# 18V_Jetson.net
KiCad netlist of a schematic drawn in Altium Designer
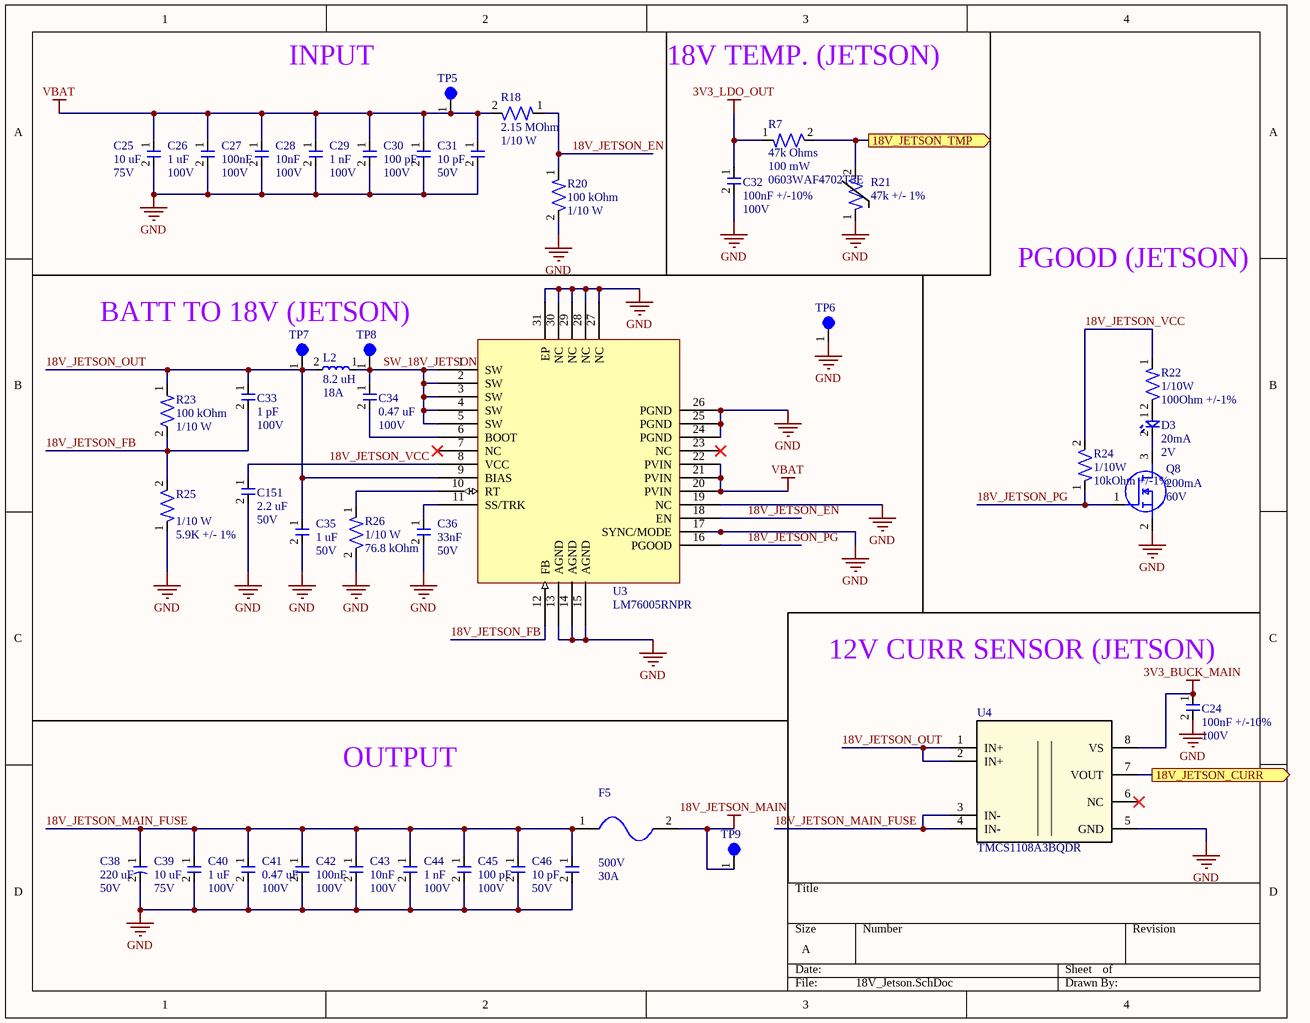
[diagram p0: 18V_Jetson.SchDoc]

(export (version "E")
  (design (tool "Eeschema 10.0.6"))
  (components
    (comp (ref "C24")
      (value "CC0603KRX7R0BB104")
      (footprint "CAP-0603")
      (description "CAP CER 0.1UF 100V X7R 0603")
      (fields
        (field (name "MANUFACTURER") "YAGEO")
        (field (name "CAPACITANCE") "100nF +/-10%")
        (field (name "VOLTAGE RATING") "100V")
      )
      (libsource (lib "MasterLib") (part "CAP-100N-0001"))
    )
    (comp (ref "C25")
      (value "C3225X7R1N106K250AC")
      (footprint "CAP-1210")
      (description "10 µF ±10% 75V Ceramic Capacitor X7R 1210 (3225 Metric)")
      (fields (field (name "CAPACITANCE") "10 uF") (field (name "VOLTAGE RATING") "75V"))
      (libsource (lib "MasterLib") (part "CAP-10U-0004"))
    )
    (comp (ref "C26")
      (value "CL31B105KCHNNNE")
      (footprint "CAP-1206 - duplicate")
      (description "1 µF ±10% 100V Ceramic Capacitor X7R 1206 (3216 Metric)")
      (fields (field (name "CAPACITANCE") "1 uF") (field (name "VOLTAGE") "100V"))
      (libsource (lib "MasterLib") (part "CAP-1U-0001"))
    )
    (comp (ref "C27")
      (value "CC0603KRX7R0BB104")
      (footprint "CAP-0603")
      (description "CAP CER 0.1UF 100V X7R 0603")
      (fields
        (field (name "MANUFACTURER") "YAGEO")
        (field (name "CAPACITANCE") "100nF")
        (field (name "VOLTAGE RATING") "100V")
      )
      (libsource (lib "MasterLib") (part "CAP-100N-0001"))
    )
    (comp (ref "C28")
      (value "C1608C0G2A103J080AC")
      (footprint "CAP-0603")
      (description "CAP CER 10000PF 100V C0G 0603")
      (fields
        (field (name "MANUFACTURER") "TDK Corporation")
        (field (name "CAPACITANCE") "10nF")
        (field (name "VOLTAGE RATING") "100V")
      )
      (libsource (lib "MasterLib") (part "CAP-10N-0002"))
    )
    (comp (ref "C29")
      (value "C0603Y102K1RAC7867")
      (footprint "CAP-0603")
      (description "1000 pF ±10% 100V Ceramic Capacitor X7R 0603 (1608 Metric)")
      (fields (field (name "CAPACITANCE") "1 nF") (field (name "VOLTAGE") "100V"))
      (libsource (lib "MasterLib") (part "CAP-1N-0001"))
    )
    (comp (ref "C30")
      (value "0603N101J101CT")
      (footprint "CAP-0603")
      (description "100 pF ±5% 100V Ceramic Capacitor C0G, NP0 0603 (1608 Metric)")
      (fields
        (field (name "TOLERANCE") "+/-5%")
        (field (name "CAPACITANCE") "100 pF")
        (field (name "VOLTAGE") "100V")
      )
      (libsource (lib "MasterLib") (part "CAP-100P-0002"))
    )
    (comp (ref "C31")
      (value "0603N100J500CT")
      (footprint "CAP-0603")
      (description "10 pF ±5% 50V Ceramic Capacitor C0G, NP0 0603 (1608 Metric)")
      (fields
        (field (name "MANUFACTURER") "Walshin Technology Corporation")
        (field (name "CAPACITANCE") "10 pF")
        (field (name "VOLTAGE RATING") "50V")
      )
      (libsource (lib "MasterLib") (part "CAP-10P-0001"))
    )
    (comp (ref "C32")
      (value "CC0603KRX7R0BB104")
      (footprint "CAP-0603")
      (description "CAP CER 0.1UF 100V X7R 0603")
      (fields
        (field (name "MANUFACTURER") "YAGEO")
        (field (name "CAPACITANCE") "100nF +/-10%")
        (field (name "VOLTAGE RATING") "100V")
      )
      (libsource (lib "MasterLib") (part "CAP-100N-0001"))
    )
    (comp (ref "C33")
      (value "885012006087")
      (footprint "CAP-0603")
      (description "1 pF ±0.25pF 100V Ceramic Capacitor C0G, NP0 0603 (1608 Metric)")
      (fields
        (field (name "TOLERANCE") "+/- 0.25 pF")
        (field (name "CAPACITANCE") "1 pF")
        (field (name "VOLTAGE") "100V")
      )
      (libsource (lib "MasterLib") (part "CAP-1P-0001"))
    )
    (comp (ref "C34")
      (value "KAM21KR72A474KL")
      (footprint "CAP-0805")
      (description "0.47 µF ±10% 100V Ceramic Capacitor X7R 0805 (2012 Metric)")
      (fields
        (field (name "TOLERANCE") "+/- 10%")
        (field (name "CAPACITANCE") "0.47 uF")
        (field (name "VOLTAGE") "100V")
      )
      (libsource (lib "MasterLib") (part "CAP-0.47U-0001"))
    )
    (comp (ref "C35")
      (value "UMK107AB7105KA-T")
      (footprint "CAP-0603")
      (description "1 µF ±10% 50V Ceramic Capacitor X7R 0603 (1608 Metric)")
      (fields (field (name "CAPACITANCE") "1 uF") (field (name "VOLTAGE") "50V"))
      (libsource (lib "MasterLib") (part "CAP-1U-0002"))
    )
    (comp (ref "C36")
      (value "CC0603KRX7R9BB333")
      (footprint "CAP-0603")
      (description "0.033 µF ±10% 50V Ceramic Capacitor X7R 0603 (1608 Metric)")
      (fields
        (field (name "MANUFACTURER") "YAGEO")
        (field (name "CAPACITANCE") "33nF")
        (field (name "VOLTAGE RATING") "50V")
      )
      (libsource (lib "MasterLib") (part "CAP-33N-0001"))
    )
    (comp (ref "C38")
      (value "50TZV220M10X10.5")
      (footprint "ELEC-220U-0003")
      (description "220 µF 50 V Aluminum Electrolytic Capacitors Radial, Can - SMD 2000 Hrs @ 105°C")
      (fields (field (name "CAPACITANCE") "220 uF") (field (name "VOLTAGE RATING") "50V"))
      (libsource (lib "MasterLib") (part "ELEC-220U-0003"))
    )
    (comp (ref "C39")
      (value "C3225X7R1N106K250AC")
      (footprint "CAP-1210")
      (description "10 µF ±10% 75V Ceramic Capacitor X7R 1210 (3225 Metric)")
      (fields (field (name "CAPACITANCE") "10 uF") (field (name "VOLTAGE RATING") "75V"))
      (libsource (lib "MasterLib") (part "CAP-10U-0004"))
    )
    (comp (ref "C40")
      (value "CL31B105KCHNNNE")
      (footprint "CAP-1206 - duplicate")
      (description "1 µF ±10% 100V Ceramic Capacitor X7R 1206 (3216 Metric)")
      (fields (field (name "CAPACITANCE") "1 uF") (field (name "VOLTAGE") "100V"))
      (libsource (lib "MasterLib") (part "CAP-1U-0001"))
    )
    (comp (ref "C41")
      (value "KAM21KR72A474KL")
      (footprint "CAP-0805")
      (description "0.47 µF ±10% 100V Ceramic Capacitor X7R 0805 (2012 Metric)")
      (fields
        (field (name "TOLERANCE") "+/- 10%")
        (field (name "CAPACITANCE") "0.47 uF")
        (field (name "VOLTAGE") "100V")
      )
      (libsource (lib "MasterLib") (part "CAP-0.47U-0001"))
    )
    (comp (ref "C42")
      (value "CC0603KRX7R0BB104")
      (footprint "CAP-0603")
      (description "CAP CER 0.1UF 100V X7R 0603")
      (fields
        (field (name "MANUFACTURER") "YAGEO")
        (field (name "CAPACITANCE") "100nF")
        (field (name "VOLTAGE RATING") "100V")
      )
      (libsource (lib "MasterLib") (part "CAP-100N-0001"))
    )
    (comp (ref "C43")
      (value "C1608C0G2A103J080AC")
      (footprint "CAP-0603")
      (description "CAP CER 10000PF 100V C0G 0603")
      (fields
        (field (name "MANUFACTURER") "TDK Corporation")
        (field (name "CAPACITANCE") "10nF")
        (field (name "VOLTAGE RATING") "100V")
      )
      (libsource (lib "MasterLib") (part "CAP-10N-0002"))
    )
    (comp (ref "C44")
      (value "C0603Y102K1RAC7867")
      (footprint "CAP-0603")
      (description "1000 pF ±10% 100V Ceramic Capacitor X7R 0603 (1608 Metric)")
      (fields (field (name "CAPACITANCE") "1 nF") (field (name "VOLTAGE") "100V"))
      (libsource (lib "MasterLib") (part "CAP-1N-0001"))
    )
    (comp (ref "C45")
      (value "0603N101J101CT")
      (footprint "CAP-0603")
      (description "100 pF ±5% 100V Ceramic Capacitor C0G, NP0 0603 (1608 Metric)")
      (fields
        (field (name "TOLERANCE") "+/-5%")
        (field (name "CAPACITANCE") "100 pF")
        (field (name "VOLTAGE") "100V")
      )
      (libsource (lib "MasterLib") (part "CAP-100P-0002"))
    )
    (comp (ref "C46")
      (value "0603N100J500CT")
      (footprint "CAP-0603")
      (description "10 pF ±5% 50V Ceramic Capacitor C0G, NP0 0603 (1608 Metric)")
      (fields
        (field (name "MANUFACTURER") "Walshin Technology Corporation")
        (field (name "CAPACITANCE") "10 pF")
        (field (name "VOLTAGE RATING") "50V")
      )
      (libsource (lib "MasterLib") (part "CAP-10P-0001"))
    )
    (comp (ref "C151")
      (value "UMK107BBJ225KA-T")
      (footprint "CAP-0603")
      (description "2.2 µF ±10% 50V Ceramic Capacitor X5R 0603 (1608 Metric)")
      (fields (field (name "CAPACITANCE") "2.2 uF") (field (name "OLTAGE") "50V"))
      (libsource (lib "MasterLib") (part "CAP-2.2U-0001"))
    )
    (comp (ref "D3")
      (value "150060AS75000")
      (footprint "LED-0603")
      (description "CAP CER 0.1UF 100V X7R 0603")
      (fields
        (field (name "MANUFACTURER") "Wurth Electronik")
        (field (name "CURRENT RATING") "20mA")
        (field (name "VF") "2V")
      )
      (libsource (lib "MasterLib") (part "LED_Amber_0001"))
    )
    (comp (ref "F5")
      (value "3568")
      (footprint "FUSE-ATM-0001")
      (description "Fuse Holder 30 A 500V 1 Circuit Blade Through Hole")
      (fields (field (name "VOLTAGE RATING") "500V") (field (name "CURRENT") "30A"))
      (libsource (lib "MasterLib") (part "FUSE-ATM-0001"))
    )
    (comp (ref "L2")
      (value "IHLP6767GZER8R2M01")
      (footprint "PWRIND-8.2U-0002")
      (description "8.2 µH Shielded Molded Inductor 18 A 10.66mOhm Max Nonstandard")
      (fields
        (field (name "TOLERANCE") "+/-20%")
        (field (name "INDUCTANCE") "8.2 uH")
        (field (name "DCI") "18A")
      )
      (libsource (lib "MasterLib") (part "PWRIND-8.2U-0002"))
    )
    (comp (ref "Q8")
      (value "T2N7002AK,LM")
      (footprint "NMOS-SOT23-3")
      (description "MOSFET N-CH 60V 200MA SOT23")
      (fields
        (field (name "MANUFACTURER") "Toshiba")
        (field (name "ID-CONTINUOUS") "200mA")
        (field (name "VDS-MAX") "60V")
      )
      (libsource (lib "MasterLib") (part "NMOS-200MA-0001"))
    )
    (comp (ref "R7")
      (value "0603WAF4702T5E")
      (footprint "RES-0603")
      (description "100mW Thick Film Resistors 75V ±100ppm/℃ ±1% 47kΩ 0603 Chip Resistor - Surface Mount ROHS")
      (fields (field (name "POWER") "100mW"))
      (libsource (lib "MasterLib") (part "RES-47k-0001-JLC"))
    )
    (comp (ref "R18")
      (value "RC0603FR-072M15L")
      (footprint "RES-0603")
      (description "2.15 MOhms ±1% 0.1W, 1/10W Chip Resistor 0603 (1608 Metric) Moisture Resistant Thick Film")
      (fields
        (field (name "TOLERANCE") "+/-1%")
        (field (name "RESISTANCE") "2.15 MOhm")
        (field (name "POWER") "1/10 W")
      )
      (libsource (lib "MasterLib") (part "RES-2.15M-0001"))
    )
    (comp (ref "R20")
      (value "RC0603FR-07100KL")
      (footprint "RES-0603")
      (description "100 kOhms ±1% 0.1W, 1/10W Chip Resistor 0603 (1608 Metric) Moisture Resistant Thick Film")
      (fields
        (field (name "TOLERANCE") "+/- 1%")
        (field (name "RESISTANCE") "100 kOhm")
        (field (name "POWER") "1/10 W")
      )
      (libsource (lib "MasterLib") (part "RES-100K-0003"))
    )
    (comp (ref "R21")
      (value "TMP6431DECR")
      (footprint "RES-0402")
      (description "PTC Thermistor 47 kOhms 0402 (1006 Metric)")
      (fields (field (name "MANUFACTURER") "Texas Instruments") (field (name "RESISTANCE") "47k +/- 1%"))
      (libsource (lib "MasterLib") (part "THERM-47K-0001"))
    )
    (comp (ref "R22")
      (value "AC0603FR-10100RL")
      (footprint "RES-0603")
      (description "100 Ohms ±1% 0.1W, 1/10W Chip Resistor 0603 (1608 Metric) Automotive AEC-Q200 Thick Film")
      (fields
        (field (name "MANUFACTURER") "YAGEO")
        (field (name "POWER RATING") "1/10W")
        (field (name "RESISTANCE") "100Ohm +/-1%")
      )
      (libsource (lib "MasterLib") (part "RES-100-0002"))
    )
    (comp (ref "R23")
      (value "RC0603FR-07100KL")
      (footprint "RES-0603")
      (description "100 kOhms ±1% 0.1W, 1/10W Chip Resistor 0603 (1608 Metric) Moisture Resistant Thick Film")
      (fields
        (field (name "TOLERANCE") "+/- 1%")
        (field (name "RESISTANCE") "100 kOhm")
        (field (name "POWER") "1/10 W")
      )
      (libsource (lib "MasterLib") (part "RES-100K-0003"))
    )
    (comp (ref "R24")
      (value "RC0603FR-0710KP")
      (footprint "RES-0603")
      (description "RES SMD 10K OHM 1% 1/10W 0603")
      (fields
        (field (name "MANUFACTURER") "YAGEO")
        (field (name "POWER RATING") "1/10W")
        (field (name "RESISTANCE") "10kOhm +/-1%")
      )
      (libsource (lib "MasterLib") (part "RES-10K-0002"))
    )
    (comp (ref "R25")
      (value "RC0603FR-075K9L")
      (footprint "RES-0603")
      (description "RES 5.9K OHM 1% 1/10W 0603")
      (fields (field (name "POWER") "1/10 W") (field (name "RESISTANCE") "5.9K +/- 1%"))
      (libsource (lib "MasterLib") (part "RES-5.9K-0001"))
    )
    (comp (ref "R26")
      (value "RC0603FR-0776K8L")
      (footprint "RES-0603")
      (description "76.8 kOhms ±1% 0.1W, 1/10W Chip Resistor 0603 (1608 Metric) Moisture Resistant Thick Film")
      (fields
        (field (name "MANUFACTURER") "Yageo")
        (field (name "TOLERANCE") "+/- 1%")
        (field (name "POWER") "1/10 W")
        (field (name "RESISTANCE") "76.8 kOhm")
      )
      (libsource (lib "MasterLib") (part "RES-76.8K-0001"))
    )
    (comp (ref "TP5")
      (value "5003")
      (footprint "TEST-POINT-0001")
      (description "Oranange PC Test Point, Miniature Phoisphor Bronze Silver Plating Through Hole Mounting Type")
      (libsource (lib "MasterLib") (part "TEST-POINT-0001"))
    )
    (comp (ref "TP6")
      (value "5003")
      (footprint "TEST-POINT-0001")
      (description "Oranange PC Test Point, Miniature Phoisphor Bronze Silver Plating Through Hole Mounting Type")
      (libsource (lib "MasterLib") (part "TEST-POINT-0001"))
    )
    (comp (ref "TP7")
      (value "5003")
      (footprint "TEST-POINT-0001")
      (description "Oranange PC Test Point, Miniature Phoisphor Bronze Silver Plating Through Hole Mounting Type")
      (libsource (lib "MasterLib") (part "TEST-POINT-0001"))
    )
    (comp (ref "TP8")
      (value "5003")
      (footprint "TEST-POINT-0001")
      (description "Oranange PC Test Point, Miniature Phoisphor Bronze Silver Plating Through Hole Mounting Type")
      (libsource (lib "MasterLib") (part "TEST-POINT-0001"))
    )
    (comp (ref "TP9")
      (value "5003")
      (footprint "TEST-POINT-0001")
      (description "Oranange PC Test Point, Miniature Phoisphor Bronze Silver Plating Through Hole Mounting Type")
      (libsource (lib "MasterLib") (part "TEST-POINT-0001"))
    )
    (comp (ref "U3")
      (value "LM76005RNPR")
      (footprint "IC-30-WQFN(6x4)")
      (description "Buck Switching Regulator IC Positive Adjustable 1V 1 Output 5A 30-WFQFN Exposed Pad")
      (fields (field (name "MANUFACTURER") "Texas Instruments") (field (name "CURRENT") "LM76005RNPR"))
      (libsource (lib "MasterLib") (part "IC-BUCK-0006"))
    )
    (comp (ref "U4")
      (value "TMCS1108A3BQDR")
      (footprint "D0008A-IPC_A")
      (libsource (lib "MasterLib") (part "IC-CURRENT-0005"))
    )
  )
  (nets
    (net (code "1") (name "/18V_JETSON_CURR") (class "Default")
      (node (ref "U4") (pin "7") (pinfunction "VOUT_7") (pintype "passive"))
    )
    (net (code "2") (name "/18V_JETSON_EN") (class "Default")
      (node (ref "R18") (pin "1") (pinfunction "1_1") (pintype "passive"))
      (node (ref "R20") (pin "1") (pinfunction "1_1") (pintype "passive"))
      (node (ref "U3") (pin "18") (pinfunction "EN_18") (pintype "power_in"))
    )
    (net (code "3") (name "/18V_JETSON_FB") (class "Default")
      (node (ref "C33") (pin "2") (pinfunction "2_2") (pintype "passive"))
      (node (ref "R23") (pin "2") (pinfunction "2_2") (pintype "passive"))
      (node (ref "R25") (pin "2") (pinfunction "2_2") (pintype "passive"))
      (node (ref "U3") (pin "12") (pinfunction "FB_12") (pintype "input"))
    )
    (net (code "4") (name "/18V_JETSON_MAIN_FUSE") (class "Default")
      (node (ref "C38") (pin "1") (pinfunction "1_1") (pintype "passive"))
      (node (ref "C39") (pin "1") (pinfunction "1_1") (pintype "passive"))
      (node (ref "C40") (pin "1") (pinfunction "1_1") (pintype "passive"))
      (node (ref "C41") (pin "1") (pinfunction "1_1") (pintype "passive"))
      (node (ref "C42") (pin "1") (pinfunction "1_1") (pintype "passive"))
      (node (ref "C43") (pin "1") (pinfunction "1_1") (pintype "passive"))
      (node (ref "C44") (pin "1") (pinfunction "1_1") (pintype "passive"))
      (node (ref "C45") (pin "1") (pinfunction "1_1") (pintype "passive"))
      (node (ref "C46") (pin "1") (pinfunction "1_1") (pintype "passive"))
      (node (ref "F5") (pin "1") (pinfunction "0_1") (pintype "passive"))
      (node (ref "U4") (pin "3") (pinfunction "IN-_3") (pintype "passive"))
      (node (ref "U4") (pin "4") (pinfunction "IN-_4") (pintype "passive"))
    )
    (net (code "5") (name "/18V_JETSON_OUT") (class "Default")
      (node (ref "C33") (pin "1") (pinfunction "1_1") (pintype "passive"))
      (node (ref "C35") (pin "1") (pinfunction "1_1") (pintype "passive"))
      (node (ref "L2") (pin "2") (pinfunction "2_2") (pintype "passive"))
      (node (ref "R23") (pin "1") (pinfunction "1_1") (pintype "passive"))
      (node (ref "TP7") (pin "1") (pinfunction "0_1") (pintype "passive"))
      (node (ref "U3") (pin "9") (pinfunction "BIAS_9") (pintype "power_in"))
      (node (ref "U4") (pin "1") (pinfunction "IN+_1") (pintype "passive"))
      (node (ref "U4") (pin "2") (pinfunction "IN+_2") (pintype "passive"))
    )
    (net (code "6") (name "/18V_JETSON_PG") (class "Default")
      (node (ref "Q8") (pin "1") (pinfunction "G_1") (pintype "passive"))
      (node (ref "R24") (pin "1") (pinfunction "1_1") (pintype "passive"))
      (node (ref "U3") (pin "16") (pinfunction "PGOOD_16") (pintype "power_in"))
    )
    (net (code "7") (name "/18V_JETSON_TMP") (class "Default")
      (node (ref "R21") (pin "2") (pinfunction "2_2") (pintype "passive"))
      (node (ref "R7") (pin "2") (pinfunction "2_2") (pintype "passive"))
    )
    (net (code "8") (name "/18V_JETSON_VCC") (class "Default")
      (node (ref "C151") (pin "1") (pinfunction "1_1") (pintype "passive"))
      (node (ref "R22") (pin "1") (pinfunction "1_1") (pintype "passive"))
      (node (ref "R24") (pin "2") (pinfunction "2_2") (pintype "passive"))
      (node (ref "U3") (pin "8") (pinfunction "VCC_8") (pintype "power_in"))
    )
    (net (code "9") (name "/SW_18V_JETSON") (class "Default")
      (node (ref "C34") (pin "1") (pinfunction "1_1") (pintype "passive"))
      (node (ref "L2") (pin "1") (pinfunction "1_1") (pintype "passive"))
      (node (ref "TP8") (pin "1") (pinfunction "0_1") (pintype "passive"))
      (node (ref "U3") (pin "1") (pinfunction "SW_1") (pintype "power_in"))
      (node (ref "U3") (pin "2") (pinfunction "SW_2") (pintype "power_in"))
      (node (ref "U3") (pin "3") (pinfunction "SW_3") (pintype "power_in"))
      (node (ref "U3") (pin "4") (pinfunction "SW_4") (pintype "power_in"))
      (node (ref "U3") (pin "5") (pinfunction "SW_5") (pintype "power_in"))
    )
    (net (code "10") (name "3V3_BUCK_MAIN") (class "Default")
      (node (ref "C24") (pin "1") (pinfunction "1_1") (pintype "passive"))
      (node (ref "U4") (pin "8") (pinfunction "VS_8") (pintype "power_in"))
    )
    (net (code "11") (name "3V3_LDO_OUT") (class "Default")
      (node (ref "C32") (pin "1") (pinfunction "1_1") (pintype "passive"))
      (node (ref "R7") (pin "1") (pinfunction "1_1") (pintype "passive"))
    )
    (net (code "12") (name "18V_JETSON_MAIN") (class "Default")
      (node (ref "F5") (pin "2") (pinfunction "1_2") (pintype "passive"))
      (node (ref "TP9") (pin "1") (pinfunction "0_1") (pintype "passive"))
    )
    (net (code "13") (name "GND") (class "Default")
      (node (ref "C151") (pin "2") (pinfunction "2_2") (pintype "passive"))
      (node (ref "C24") (pin "2") (pinfunction "2_2") (pintype "passive"))
      (node (ref "C25") (pin "2") (pinfunction "2_2") (pintype "passive"))
      (node (ref "C26") (pin "2") (pinfunction "2_2") (pintype "passive"))
      (node (ref "C27") (pin "2") (pinfunction "2_2") (pintype "passive"))
      (node (ref "C28") (pin "2") (pinfunction "2_2") (pintype "passive"))
      (node (ref "C29") (pin "2") (pinfunction "2_2") (pintype "passive"))
      (node (ref "C30") (pin "2") (pinfunction "2_2") (pintype "passive"))
      (node (ref "C31") (pin "2") (pinfunction "2_2") (pintype "passive"))
      (node (ref "C32") (pin "2") (pinfunction "2_2") (pintype "passive"))
      (node (ref "C35") (pin "2") (pinfunction "2_2") (pintype "passive"))
      (node (ref "C36") (pin "2") (pinfunction "2_2") (pintype "passive"))
      (node (ref "C38") (pin "2") (pinfunction "2_2") (pintype "passive"))
      (node (ref "C39") (pin "2") (pinfunction "2_2") (pintype "passive"))
      (node (ref "C40") (pin "2") (pinfunction "2_2") (pintype "passive"))
      (node (ref "C41") (pin "2") (pinfunction "2_2") (pintype "passive"))
      (node (ref "C42") (pin "2") (pinfunction "2_2") (pintype "passive"))
      (node (ref "C43") (pin "2") (pinfunction "2_2") (pintype "passive"))
      (node (ref "C44") (pin "2") (pinfunction "2_2") (pintype "passive"))
      (node (ref "C45") (pin "2") (pinfunction "2_2") (pintype "passive"))
      (node (ref "C46") (pin "2") (pinfunction "2_2") (pintype "passive"))
      (node (ref "Q8") (pin "2") (pinfunction "S_2") (pintype "passive"))
      (node (ref "R20") (pin "2") (pinfunction "2_2") (pintype "passive"))
      (node (ref "R21") (pin "1") (pinfunction "1_1") (pintype "passive"))
      (node (ref "R25") (pin "1") (pinfunction "1_1") (pintype "passive"))
      (node (ref "R26") (pin "2") (pinfunction "2_2") (pintype "passive"))
      (node (ref "TP6") (pin "1") (pinfunction "0_1") (pintype "passive"))
      (node (ref "U3") (pin "13") (pinfunction "AGND_13") (pintype "power_in"))
      (node (ref "U3") (pin "14") (pinfunction "AGND_14") (pintype "power_in"))
      (node (ref "U3") (pin "15") (pinfunction "AGND_15") (pintype "power_in"))
      (node (ref "U3") (pin "17") (pinfunction "SYNC/MODE_17") (pintype "power_in"))
      (node (ref "U3") (pin "19") (pinfunction "NC_19") (pintype "power_in"))
      (node (ref "U3") (pin "24") (pinfunction "PGND_24") (pintype "power_in"))
      (node (ref "U3") (pin "25") (pinfunction "PGND_25") (pintype "power_in"))
      (node (ref "U3") (pin "26") (pinfunction "PGND_26") (pintype "power_in"))
      (node (ref "U3") (pin "27") (pinfunction "NC_27") (pintype "power_in"))
      (node (ref "U3") (pin "28") (pinfunction "NC_28") (pintype "power_in"))
      (node (ref "U3") (pin "29") (pinfunction "NC_29") (pintype "power_in"))
      (node (ref "U3") (pin "30") (pinfunction "NC_30") (pintype "power_in"))
      (node (ref "U3") (pin "31") (pinfunction "EP_31") (pintype "power_in"))
      (node (ref "U4") (pin "5") (pinfunction "GND_5") (pintype "power_in"))
    )
    (net (code "14") (name "Net-(D3-Pad1)") (class "Default")
      (node (ref "D3") (pin "1") (pinfunction "1_1") (pintype "passive"))
      (node (ref "R22") (pin "2") (pinfunction "2_2") (pintype "passive"))
    )
    (net (code "15") (name "Net-(Q8-D)") (class "Default")
      (node (ref "D3") (pin "2") (pinfunction "2_2") (pintype "passive"))
      (node (ref "Q8") (pin "3") (pinfunction "D_3") (pintype "passive"))
    )
    (net (code "16") (name "Net-(U3-BOOT)") (class "Default")
      (node (ref "C34") (pin "2") (pinfunction "2_2") (pintype "passive"))
      (node (ref "U3") (pin "6") (pinfunction "BOOT_6") (pintype "power_in"))
    )
    (net (code "17") (name "Net-(U3-RT)") (class "Default")
      (node (ref "R26") (pin "1") (pinfunction "1_1") (pintype "passive"))
      (node (ref "U3") (pin "10") (pinfunction "RT_10") (pintype "bidirectional"))
    )
    (net (code "18") (name "Net-(U3-SS{slash}TRK)") (class "Default")
      (node (ref "C36") (pin "1") (pinfunction "1_1") (pintype "passive"))
      (node (ref "U3") (pin "11") (pinfunction "SS/TRK_11") (pintype "passive"))
    )
    (net (code "19") (name "VBAT") (class "Default")
      (node (ref "C25") (pin "1") (pinfunction "1_1") (pintype "passive"))
      (node (ref "C26") (pin "1") (pinfunction "1_1") (pintype "passive"))
      (node (ref "C27") (pin "1") (pinfunction "1_1") (pintype "passive"))
      (node (ref "C28") (pin "1") (pinfunction "1_1") (pintype "passive"))
      (node (ref "C29") (pin "1") (pinfunction "1_1") (pintype "passive"))
      (node (ref "C30") (pin "1") (pinfunction "1_1") (pintype "passive"))
      (node (ref "C31") (pin "1") (pinfunction "1_1") (pintype "passive"))
      (node (ref "R18") (pin "2") (pinfunction "2_2") (pintype "passive"))
      (node (ref "TP5") (pin "1") (pinfunction "0_1") (pintype "passive"))
      (node (ref "U3") (pin "20") (pinfunction "PVIN_20") (pintype "power_in"))
      (node (ref "U3") (pin "21") (pinfunction "PVIN_21") (pintype "power_in"))
      (node (ref "U3") (pin "22") (pinfunction "PVIN_22") (pintype "power_in"))
    )
    (net (code "20") (name "unconnected-(U3-NC-Pad7)") (class "Default")
      (node (ref "U3") (pin "7") (pinfunction "NC_7") (pintype "power_in+no_connect"))
    )
    (net (code "21") (name "unconnected-(U3-NC-Pad23)") (class "Default")
      (node (ref "U3") (pin "23") (pinfunction "NC_23") (pintype "tri_state+no_connect"))
    )
    (net (code "22") (name "unconnected-(U4-NC-Pad6)") (class "Default")
      (node (ref "U4") (pin "6") (pinfunction "NC_6") (pintype "passive+no_connect"))
    )
  )
)
